# ACCTRL_OPTOTRIAC.net
KiCad netlist of a schematic drawn in Altium Designer
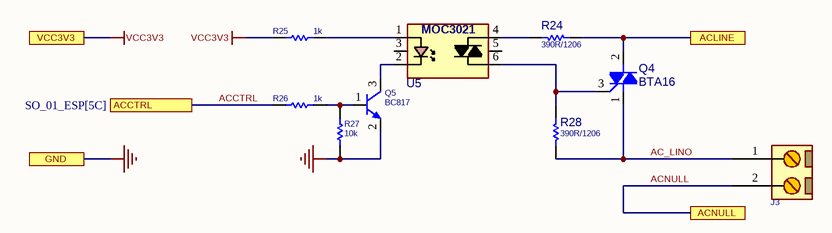
[diagram p0: ACCTRL_OPTOTRIAC.SchDoc]

(export (version "E")
  (design (tool "Eeschema 10.0.6"))
  (components
    (comp (ref "J3")
      (value "CONN_TB2")
      (footprint "MSTB_2")
      (description "CONN, PHOENIX MSTB, 5-G, 5.08mm pitch")
      (libsource (lib "conn_power_terminalB") (part "CONN_MSTB_2"))
    )
    (comp (ref "Q4")
      (value "BTA16")
      (footprint "TO220_3")
      (description "Triac, 800V, 16A, TO-220")
      (fields (field (name "MANF_P#") "BTA16-800CW") (field (name "MANF") "ST"))
      (libsource (lib "triac_diac") (part "TRIAC_BTA16-800_TO220"))
    )
    (comp (ref "Q5")
      (value "BC817")
      (footprint "SOT23_3")
      (description "BJT, NPN, 45v, 0.5A, SMD, SOT23")
      (fields (field (name "MANF") "NXP, ON"))
      (libsource (lib "transistor_bjt") (part "NPN_BC817_SOT23"))
    )
    (comp (ref "R24")
      (value "390R/1206")
      (footprint "R1206")
      (description "RESISTOR, SMD, 1206")
      (libsource (lib "passive_smd") (part "RES_SMD_1206"))
    )
    (comp (ref "R25")
      (value "1k")
      (footprint "R0603")
      (description "RESISTOR, SMD")
      (libsource (lib "passive_smd") (part "RES_SMD_0603"))
    )
    (comp (ref "R26")
      (value "1k")
      (footprint "R0603")
      (description "RESISTOR, SMD")
      (libsource (lib "passive_smd") (part "RES_SMD_0603"))
    )
    (comp (ref "R27")
      (value "10k")
      (footprint "R0603")
      (description "RESISTOR, SMD")
      (libsource (lib "passive_smd") (part "RES_SMD_0603"))
    )
    (comp (ref "R28")
      (value "390R/1206")
      (footprint "R1206")
      (description "RESISTOR, SMD, 1206")
      (libsource (lib "passive_smd") (part "RES_SMD_1206"))
    )
    (comp (ref "U5")
      (value "MOC3021")
      (footprint "DIP_6SMD")
      (description "OPTOTRIAC, 400v/1A")
      (fields (field (name "MANF_P#") "MOC3021-3"))
      (libsource (lib "optocoupler") (part "OPT_TRIAC6P_MOC3021_SMD"))
    )
  )
  (nets
    (net (code "1") (name "/ACCTRL") (class "Default")
      (node (ref "R26") (pin "1") (pinfunction "1_1") (pintype "passive"))
    )
    (net (code "2") (name "/ACLINE") (class "Default")
      (node (ref "Q4") (pin "2") (pinfunction "T2_2") (pintype "passive"))
      (node (ref "R24") (pin "1") (pinfunction "1_1") (pintype "passive"))
    )
    (net (code "3") (name "/ACNULL") (class "Default")
      (node (ref "J3") (pin "2") (pinfunction "2_2") (pintype "passive"))
    )
    (net (code "4") (name "/AC_LINO") (class "Default")
      (node (ref "J3") (pin "1") (pinfunction "1_1") (pintype "passive"))
      (node (ref "Q4") (pin "1") (pinfunction "T1_1") (pintype "passive"))
      (node (ref "R28") (pin "1") (pinfunction "1_1") (pintype "passive"))
    )
    (net (code "5") (name "GND") (class "Default")
      (node (ref "Q5") (pin "2") (pinfunction "E_2") (pintype "passive"))
      (node (ref "R27") (pin "1") (pinfunction "1_1") (pintype "passive"))
    )
    (net (code "6") (name "Net-(Q4-G)") (class "Default")
      (node (ref "Q4") (pin "3") (pinfunction "G_3") (pintype "passive"))
      (node (ref "R28") (pin "2") (pinfunction "2_2") (pintype "passive"))
      (node (ref "U5") (pin "6") (pinfunction "A/K_6") (pintype "passive"))
    )
    (net (code "7") (name "Net-(Q5-B)") (class "Default")
      (node (ref "Q5") (pin "1") (pinfunction "B_1") (pintype "passive"))
      (node (ref "R26") (pin "2") (pinfunction "2_2") (pintype "passive"))
      (node (ref "R27") (pin "2") (pinfunction "2_2") (pintype "passive"))
    )
    (net (code "8") (name "Net-(Q5-C)") (class "Default")
      (node (ref "Q5") (pin "3") (pinfunction "C_3") (pintype "passive"))
      (node (ref "U5") (pin "2") (pinfunction "K_2") (pintype "passive"))
    )
    (net (code "9") (name "Net-(R24-Pad2)") (class "Default")
      (node (ref "R24") (pin "2") (pinfunction "2_2") (pintype "passive"))
      (node (ref "U5") (pin "4") (pinfunction "A/K_4") (pintype "passive"))
    )
    (net (code "10") (name "Net-(U5-A)") (class "Default")
      (node (ref "R25") (pin "2") (pinfunction "2_2") (pintype "passive"))
      (node (ref "U5") (pin "1") (pinfunction "A_1") (pintype "passive"))
    )
    (net (code "11") (name "VCC3V3") (class "Default")
      (node (ref "R25") (pin "1") (pinfunction "1_1") (pintype "passive"))
    )
    (net (code "12") (name "unconnected-(U5-NC-Pad3)") (class "Default")
      (node (ref "U5") (pin "3") (pinfunction "NC_3") (pintype "passive"))
    )
    (net (code "13") (name "unconnected-(U5-NC-Pad5)") (class "Default")
      (node (ref "U5") (pin "5") (pinfunction "NC_5") (pintype "passive"))
    )
  )
)
